# GPS.net
KiCad netlist of a schematic drawn in Altium Designer
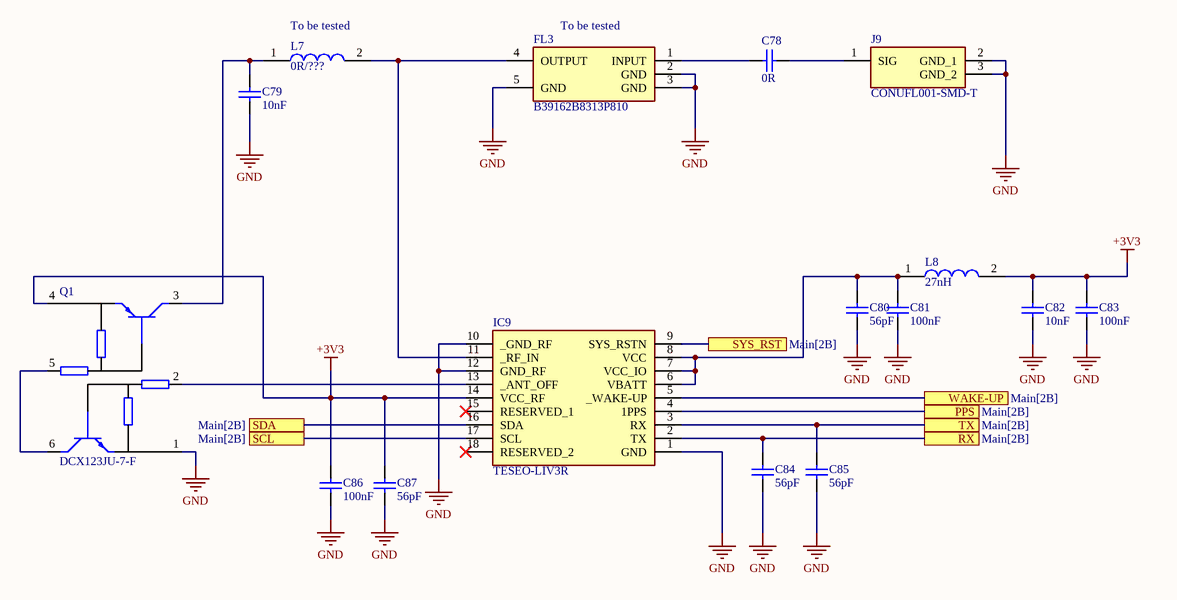
[diagram p0: GPS.SchDoc]

(export (version "E")
  (design (tool "Eeschema 10.0.6"))
  (components
    (comp (ref "C78")
      (value "0R")
      (footprint "CAP0402")
      (description "RF NP0")
      (fields (field (name "Comment") "Cap0402"))
      (libsource (lib "capacitorsSMD") (part "Cap0402"))
    )
    (comp (ref "C79")
      (value "10nF")
      (footprint "CAP0402")
      (description "RF NP0")
      (fields (field (name "VOLTAGE") "50V") (field (name "MANUFACTURER_PART_NUMBER") "GRM1555CYA103GE01D"))
      (libsource (lib "capacitorsSMD") (part "Cap0402"))
    )
    (comp (ref "C80")
      (value "56pF")
      (footprint "CAP0402")
      (fields
        (field (name "VOLTAGE") "50V")
        (field (name "MANUFACTURER_PART_NUMBER") "GCM1555C1H560GA16D")
        (field (name "Comment") "Cap0402")
      )
      (libsource (lib "capacitorsSMD") (part "Cap0402"))
    )
    (comp (ref "C81")
      (value "100nF")
      (footprint "CAP0402")
      (fields
        (field (name "VOLTAGE") "50V")
        (field (name "MANUFACTURER_PART_NUMBER") "GRM155R71H104ME14D")
        (field (name "Comment") "Cap0402")
      )
      (libsource (lib "capacitorsSMD") (part "Cap0402"))
    )
    (comp (ref "C82")
      (value "10nF")
      (footprint "CAP0402")
      (fields
        (field (name "VOLTAGE") "50V")
        (field (name "MANUFACTURER_PART_NUMBER") "GRM155R71H103MA88D")
        (field (name "Comment") "Cap0402")
      )
      (libsource (lib "capacitorsSMD") (part "Cap0402"))
    )
    (comp (ref "C83")
      (value "100nF")
      (footprint "CAP0402")
      (fields
        (field (name "VOLTAGE") "50V")
        (field (name "MANUFACTURER_PART_NUMBER") "GRM155R71H104ME14D")
        (field (name "Comment") "Cap0402")
      )
      (libsource (lib "capacitorsSMD") (part "Cap0402"))
    )
    (comp (ref "C84")
      (value "56pF")
      (footprint "CAP0402")
      (fields
        (field (name "VOLTAGE") "50V")
        (field (name "MANUFACTURER_PART_NUMBER") "GCM1555C1H560GA16D")
        (field (name "Comment") "Cap0402")
      )
      (libsource (lib "capacitorsSMD") (part "Cap0402"))
    )
    (comp (ref "C85")
      (value "56pF")
      (footprint "CAP0402")
      (fields
        (field (name "VOLTAGE") "50V")
        (field (name "MANUFACTURER_PART_NUMBER") "GCM1555C1H560GA16D")
        (field (name "Comment") "Cap0402")
      )
      (libsource (lib "capacitorsSMD") (part "Cap0402"))
    )
    (comp (ref "C86")
      (value "100nF")
      (footprint "CAP0402")
      (fields
        (field (name "VOLTAGE") "50V")
        (field (name "MANUFACTURER_PART_NUMBER") "GRM155R71H104ME14D")
        (field (name "Comment") "Cap0402")
      )
      (libsource (lib "capacitorsSMD") (part "Cap0402"))
    )
    (comp (ref "C87")
      (value "56pF")
      (footprint "CAP0402")
      (fields
        (field (name "VOLTAGE") "50V")
        (field (name "MANUFACTURER_PART_NUMBER") "GCM1555C1H560GA16D")
        (field (name "Comment") "Cap0402")
      )
      (libsource (lib "capacitorsSMD") (part "Cap0402"))
    )
    (comp (ref "FL3")
      (value "B39162B8313P810")
      (footprint "SamacSys:B39162B8313P810")
      (description "Filter")
      (libsource (lib "SamacSys") (part "B39162B8313P810"))
    )
    (comp (ref "IC9")
      (value "TESEO-LIV3R")
      (footprint "SamacSys:TESEOLIV3R")
      (description "Integrated Circuit")
      (fields (field (name "MOUSER PART NUMBER") "511-TESEO-LIV3R"))
      (libsource (lib "*") (part "TESEO-LIV3R"))
    )
    (comp (ref "J9")
      (value "CONUFL001-SMD-T")
      (footprint "SamacSys:CONUFL001-SMD")
      (description "Connector")
      (fields (field (name "MOUSER PART NUMBER") "712-CONUFL001-SMD-T"))
      (libsource (lib "*") (part "CONUFL001-SMD-T"))
    )
    (comp (ref "L7")
      (value "0R/???")
      (footprint "SamacSys:INDC1005X55N")
      (description "Inductor")
      (fields (field (name "MANUFACTURER_PART_NUMBER") "LQG15HS27NJ02"))
      (libsource (lib "*") (part "LQG15HS27NJ02"))
    )
    (comp (ref "L8")
      (value "27nH")
      (footprint "SamacSys:INDC1005X55N")
      (description "Inductor")
      (fields (field (name "MANUFACTURER_PART_NUMBER") "LQG15HS27NJ02"))
      (libsource (lib "*") (part "LQG15HS27NJ02"))
    )
    (comp (ref "Q1")
      (value "DCX123JU-7-F")
      (footprint "SamacSys:SOT65P210X110-6N")
      (description "Transistor BJT PNP")
      (fields (field (name "MOUSER PART NUMBER") "621-DCX123JU-F"))
      (libsource (lib "SamacSys") (part "DCX123JU-7-F"))
    )
  )
  (nets
    (net (code "1") (name "+3V3") (class "Default")
      (node (ref "C82") (pin "2") (pinfunction "2_2") (pintype "passive"))
      (node (ref "C83") (pin "2") (pinfunction "2_2") (pintype "passive"))
      (node (ref "C86") (pin "2") (pinfunction "2_2") (pintype "passive"))
      (node (ref "C87") (pin "2") (pinfunction "2_2") (pintype "passive"))
      (node (ref "IC9") (pin "14") (pinfunction "VCC_RF_14") (pintype "passive"))
      (node (ref "L8") (pin "2") (pinfunction "2_2") (pintype "passive"))
      (node (ref "Q1") (pin "4") (pinfunction "E_4") (pintype "passive"))
    )
    (net (code "2") (name "/PPS") (class "Default")
      (node (ref "IC9") (pin "4") (pinfunction "1PPS_4") (pintype "passive"))
    )
    (net (code "3") (name "/RX") (class "Default")
      (node (ref "C84") (pin "2") (pinfunction "2_2") (pintype "passive"))
      (node (ref "IC9") (pin "2") (pinfunction "TX_2") (pintype "passive"))
    )
    (net (code "4") (name "/SCL") (class "Default")
      (node (ref "IC9") (pin "17") (pinfunction "SCL_17") (pintype "passive"))
    )
    (net (code "5") (name "/SDA") (class "Default")
      (node (ref "IC9") (pin "16") (pinfunction "SDA_16") (pintype "passive"))
    )
    (net (code "6") (name "/SYS_RST") (class "Default")
      (node (ref "IC9") (pin "9") (pinfunction "SYS_RSTN_9") (pintype "passive"))
    )
    (net (code "7") (name "/TX") (class "Default")
      (node (ref "C85") (pin "2") (pinfunction "2_2") (pintype "passive"))
      (node (ref "IC9") (pin "3") (pinfunction "RX_3") (pintype "passive"))
    )
    (net (code "8") (name "/WAKE-UP") (class "Default")
      (node (ref "IC9") (pin "5") (pinfunction "_WAKE-UP_5") (pintype "passive"))
    )
    (net (code "9") (name "GND") (class "Default")
      (node (ref "C79") (pin "1") (pinfunction "1_1") (pintype "passive"))
      (node (ref "C80") (pin "1") (pinfunction "1_1") (pintype "passive"))
      (node (ref "C81") (pin "1") (pinfunction "1_1") (pintype "passive"))
      (node (ref "C82") (pin "1") (pinfunction "1_1") (pintype "passive"))
      (node (ref "C83") (pin "1") (pinfunction "1_1") (pintype "passive"))
      (node (ref "C84") (pin "1") (pinfunction "1_1") (pintype "passive"))
      (node (ref "C85") (pin "1") (pinfunction "1_1") (pintype "passive"))
      (node (ref "C86") (pin "1") (pinfunction "1_1") (pintype "passive"))
      (node (ref "C87") (pin "1") (pinfunction "1_1") (pintype "passive"))
      (node (ref "FL3") (pin "2") (pinfunction "GND_2") (pintype "passive"))
      (node (ref "FL3") (pin "3") (pinfunction "GND_3") (pintype "passive"))
      (node (ref "FL3") (pin "5") (pinfunction "GND_5") (pintype "passive"))
      (node (ref "IC9") (pin "1") (pinfunction "GND_1") (pintype "passive"))
      (node (ref "IC9") (pin "10") (pinfunction "_GND_RF_10") (pintype "passive"))
      (node (ref "IC9") (pin "12") (pinfunction "GND_RF_12") (pintype "passive"))
      (node (ref "J9") (pin "2") (pinfunction "GND_1_2") (pintype "passive"))
      (node (ref "J9") (pin "3") (pinfunction "GND_2_3") (pintype "passive"))
      (node (ref "Q1") (pin "1") (pinfunction "E_1") (pintype "passive"))
    )
    (net (code "10") (name "Net-(C79-Pad2)") (class "Default")
      (node (ref "C79") (pin "2") (pinfunction "2_2") (pintype "passive"))
      (node (ref "L7") (pin "1") (pinfunction "1_1") (pintype "passive"))
      (node (ref "Q1") (pin "3") (pinfunction "C_3") (pintype "passive"))
    )
    (net (code "11") (name "Net-(FL3-INPUT)") (class "Default")
      (node (ref "C78") (pin "2") (pinfunction "2_2") (pintype "passive"))
      (node (ref "FL3") (pin "1") (pinfunction "INPUT_1") (pintype "passive"))
    )
    (net (code "12") (name "Net-(FL3-OUTPUT)") (class "Default")
      (node (ref "FL3") (pin "4") (pinfunction "OUTPUT_4") (pintype "passive"))
      (node (ref "IC9") (pin "11") (pinfunction "_RF_IN_11") (pintype "passive"))
      (node (ref "L7") (pin "2") (pinfunction "2_2") (pintype "passive"))
    )
    (net (code "13") (name "Net-(IC9-VBATT)") (class "Default")
      (node (ref "C80") (pin "2") (pinfunction "2_2") (pintype "passive"))
      (node (ref "C81") (pin "2") (pinfunction "2_2") (pintype "passive"))
      (node (ref "IC9") (pin "6") (pinfunction "VBATT_6") (pintype "passive"))
      (node (ref "IC9") (pin "7") (pinfunction "VCC_IO_7") (pintype "passive"))
      (node (ref "IC9") (pin "8") (pinfunction "VCC_8") (pintype "passive"))
      (node (ref "L8") (pin "1") (pinfunction "1_1") (pintype "passive"))
    )
    (net (code "14") (name "Net-(IC9-_ANT_OFF)") (class "Default")
      (node (ref "IC9") (pin "13") (pinfunction "_ANT_OFF_13") (pintype "passive"))
      (node (ref "Q1") (pin "2") (pinfunction "B_2") (pintype "passive"))
    )
    (net (code "15") (name "Net-(J9-SIG)") (class "Default")
      (node (ref "C78") (pin "1") (pinfunction "1_1") (pintype "passive"))
      (node (ref "J9") (pin "1") (pinfunction "SIG_1") (pintype "passive"))
    )
    (net (code "16") (name "Net-(Q1-B-Pad5)") (class "Default")
      (node (ref "Q1") (pin "5") (pinfunction "B_5") (pintype "passive"))
      (node (ref "Q1") (pin "6") (pinfunction "C_6") (pintype "passive"))
    )
    (net (code "17") (name "unconnected-(IC9-RESERVED_1-Pad15)") (class "Default")
      (node (ref "IC9") (pin "15") (pinfunction "RESERVED_1_15") (pintype "passive+no_connect"))
    )
    (net (code "18") (name "unconnected-(IC9-RESERVED_2-Pad18)") (class "Default")
      (node (ref "IC9") (pin "18") (pinfunction "RESERVED_2_18") (pintype "passive+no_connect"))
    )
  )
)
